# Sensor_Board_0x07_Heat_Flux_v2.net
KiCad netlist of a schematic drawn in EAGLE
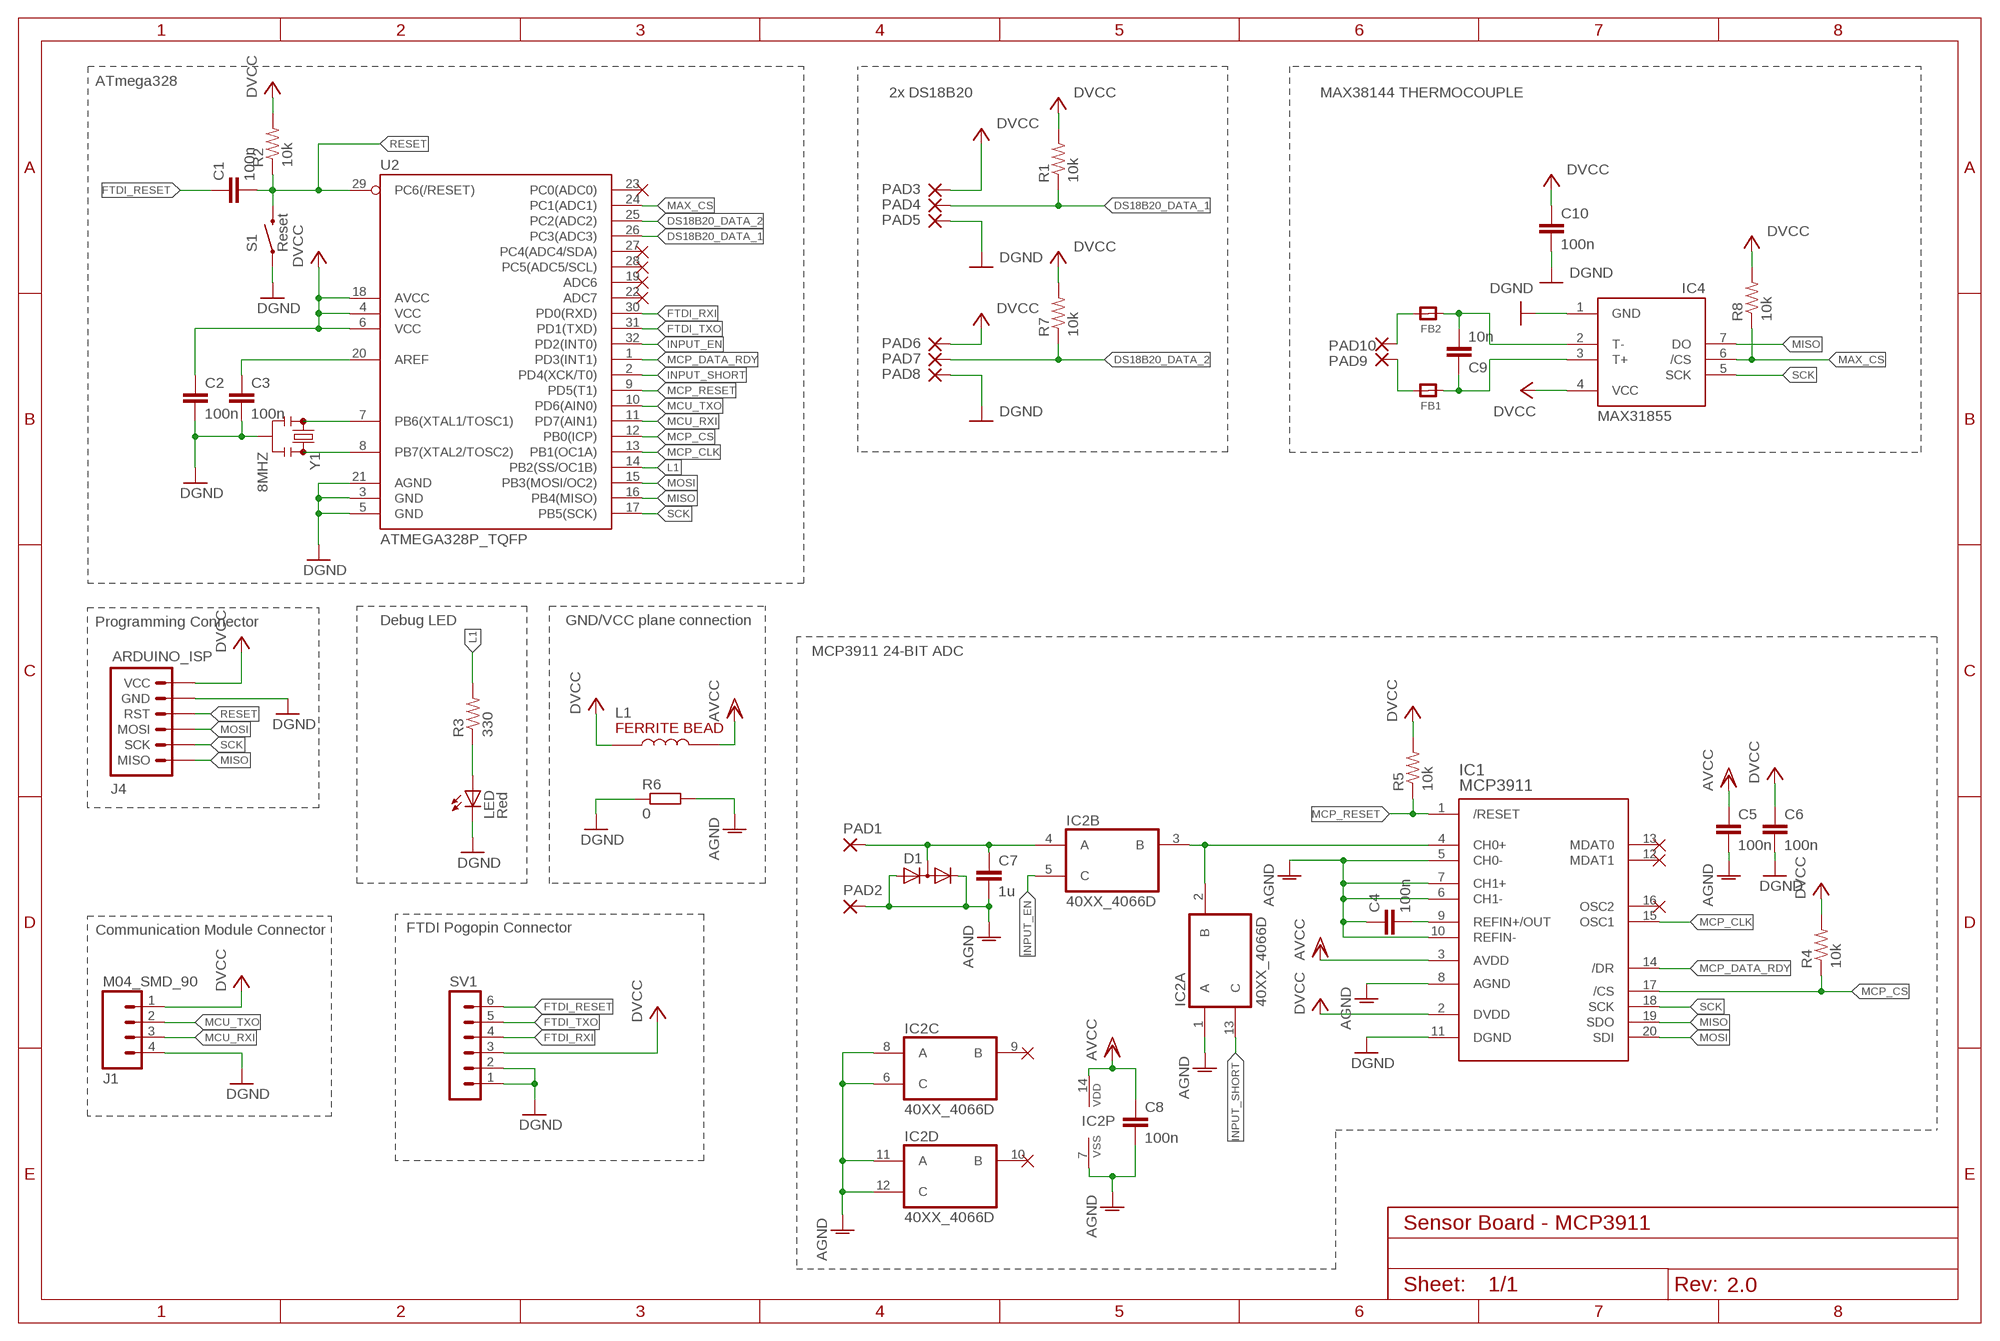
[diagram p0: schematic, sheet 1]

(export (version "E")
  (design (tool "Eeschema 10.0.6"))
  (components
    (comp (ref "C1")
      (value "100n")
      (footprint "eagle-import:C0805")
      (libsource (lib "eagle-import") (part "C"))
    )
    (comp (ref "C2")
      (value "100n")
      (footprint "eagle-import:C0805")
      (libsource (lib "eagle-import") (part "C"))
    )
    (comp (ref "C3")
      (value "100n")
      (footprint "eagle-import:C0805")
      (libsource (lib "eagle-import") (part "C"))
    )
    (comp (ref "C4")
      (value "100n")
      (footprint "eagle-import:C0805")
      (libsource (lib "eagle-import") (part "C"))
    )
    (comp (ref "C5")
      (value "100n")
      (footprint "eagle-import:C0805")
      (libsource (lib "eagle-import") (part "C"))
    )
    (comp (ref "C6")
      (value "100n")
      (footprint "eagle-import:C0805")
      (libsource (lib "eagle-import") (part "C"))
    )
    (comp (ref "C7")
      (value "1u")
      (footprint "eagle-import:C0805")
      (libsource (lib "eagle-import") (part "C"))
    )
    (comp (ref "C8")
      (value "100n")
      (footprint "eagle-import:C0805")
      (libsource (lib "eagle-import") (part "C"))
    )
    (comp (ref "C9")
      (value "10n")
      (footprint "eagle-import:C0805")
      (libsource (lib "eagle-import") (part "C"))
    )
    (comp (ref "C10")
      (value "100n")
      (footprint "eagle-import:C0805")
      (libsource (lib "eagle-import") (part "C"))
    )
    (comp (ref "D1")
      (value "LEDXLAMP_BAV99")
      (footprint "eagle-import:LEDXLAMP_SOT23")
      (libsource (lib "eagle-import") (part "LEDXLAMP_BAV99"))
    )
    (comp (ref "FB1")
      (value "MICROBUILDER_FERRITE_0805MP")
      (footprint "eagle-import:MICROBUILDER__0805MP")
      (libsource (lib "eagle-import") (part "MICROBUILDER_FERRITE_0805MP"))
    )
    (comp (ref "FB2")
      (value "MICROBUILDER_FERRITE_0805MP")
      (footprint "eagle-import:MICROBUILDER__0805MP")
      (libsource (lib "eagle-import") (part "MICROBUILDER_FERRITE_0805MP"))
    )
    (comp (ref "IC1")
      (value "MCP3911")
      (footprint "eagle-import:HEATFLOW_SSOP20")
      (libsource (lib "eagle-import") (part "HEATFLOW_MCP3911A0-E/SS"))
    )
    (comp (ref "IC2")
      (value "40XX_4066D")
      (footprint "eagle-import:40XX_SO14")
      (libsource (lib "eagle-import") (part "40XX_4066D"))
    )
    (comp (ref "IC4")
      (value "MAX31855")
      (footprint "eagle-import:ADAFRUIT_SO08")
      (libsource (lib "eagle-import") (part "ADAFRUIT_MAX31855"))
    )
    (comp (ref "J1")
      (value "M04_SMD_90")
      (footprint "eagle-import:M04_SMD_90")
      (libsource (lib "eagle-import") (part "M04_SMD_90"))
    )
    (comp (ref "J4")
      (value "ARDUINO_ISP")
      (footprint "eagle-import:M-2X3")
      (libsource (lib "eagle-import") (part "ARDUINO_ISP"))
    )
    (comp (ref "L1")
      (value "HEATFLOW2_74279220601")
      (footprint "eagle-import:HEATFLOW2_0805")
      (libsource (lib "eagle-import") (part "HEATFLOW2_74279220601"))
    )
    (comp (ref "LED")
      (value "Red")
      (footprint "eagle-import:SML0805")
      (libsource (lib "eagle-import") (part "LEDSML0805"))
    )
    (comp (ref "PAD1")
      (value "WIREPADSMD1,27-254")
      (footprint "eagle-import:SMD1,27-2,54")
      (libsource (lib "eagle-import") (part "WIREPADSMD1,27-254"))
    )
    (comp (ref "PAD2")
      (value "WIREPADSMD1,27-254")
      (footprint "eagle-import:SMD1,27-2,54")
      (libsource (lib "eagle-import") (part "WIREPADSMD1,27-254"))
    )
    (comp (ref "PAD3")
      (value "WIREPADSMD1,27-254")
      (footprint "eagle-import:SMD1,27-2,54")
      (libsource (lib "eagle-import") (part "WIREPADSMD1,27-254"))
    )
    (comp (ref "PAD4")
      (value "WIREPADSMD1,27-254")
      (footprint "eagle-import:SMD1,27-2,54")
      (libsource (lib "eagle-import") (part "WIREPADSMD1,27-254"))
    )
    (comp (ref "PAD5")
      (value "WIREPADSMD1,27-254")
      (footprint "eagle-import:SMD1,27-2,54")
      (libsource (lib "eagle-import") (part "WIREPADSMD1,27-254"))
    )
    (comp (ref "PAD6")
      (value "WIREPADSMD1,27-254")
      (footprint "eagle-import:SMD1,27-2,54")
      (libsource (lib "eagle-import") (part "WIREPADSMD1,27-254"))
    )
    (comp (ref "PAD7")
      (value "WIREPADSMD1,27-254")
      (footprint "eagle-import:SMD1,27-2,54")
      (libsource (lib "eagle-import") (part "WIREPADSMD1,27-254"))
    )
    (comp (ref "PAD8")
      (value "WIREPADSMD1,27-254")
      (footprint "eagle-import:SMD1,27-2,54")
      (libsource (lib "eagle-import") (part "WIREPADSMD1,27-254"))
    )
    (comp (ref "PAD9")
      (value "WIREPADSMD1,27-254")
      (footprint "eagle-import:SMD1,27-2,54")
      (libsource (lib "eagle-import") (part "WIREPADSMD1,27-254"))
    )
    (comp (ref "PAD10")
      (value "WIREPADSMD1,27-254")
      (footprint "eagle-import:SMD1,27-2,54")
      (libsource (lib "eagle-import") (part "WIREPADSMD1,27-254"))
    )
    (comp (ref "R1")
      (value "10k")
      (footprint "eagle-import:0805")
      (libsource (lib "eagle-import") (part "RESISTOR0805-RES"))
    )
    (comp (ref "R2")
      (value "10k")
      (footprint "eagle-import:0805")
      (libsource (lib "eagle-import") (part "RESISTOR0805-RES"))
    )
    (comp (ref "R3")
      (value "330")
      (footprint "eagle-import:0805")
      (libsource (lib "eagle-import") (part "RESISTOR0805-RES"))
    )
    (comp (ref "R4")
      (value "10k")
      (footprint "eagle-import:0805")
      (libsource (lib "eagle-import") (part "RESISTOR0805-RES"))
    )
    (comp (ref "R5")
      (value "10k")
      (footprint "eagle-import:0805")
      (libsource (lib "eagle-import") (part "RESISTOR0805-RES"))
    )
    (comp (ref "R6")
      (value "0")
      (footprint "eagle-import:RESISTOR_M0805")
      (libsource (lib "eagle-import") (part "RESISTOR_R-EU_M0805"))
    )
    (comp (ref "R7")
      (value "10k")
      (footprint "eagle-import:0805")
      (libsource (lib "eagle-import") (part "RESISTOR0805-RES"))
    )
    (comp (ref "R8")
      (value "10k")
      (footprint "eagle-import:0805")
      (libsource (lib "eagle-import") (part "RESISTOR0805-RES"))
    )
    (comp (ref "S1")
      (value "Reset")
      (footprint "eagle-import:M-PUSHBUTTON-SMD")
      (libsource (lib "eagle-import") (part "PUSHBUTTON"))
    )
    (comp (ref "SV1")
      (value "MA06-1")
      (footprint "eagle-import:MA06-1")
      (libsource (lib "eagle-import") (part "MA06-1"))
    )
    (comp (ref "U2")
      (value "ATMEGA328P_TQFP")
      (footprint "eagle-import:TQFP32-08")
      (libsource (lib "eagle-import") (part "ATMEGA328P_TQFP"))
    )
    (comp (ref "Y1")
      (value "8MHZ")
      (footprint "eagle-import:RESONATOR-SMD")
      (libsource (lib "eagle-import") (part "RESONATOR8MHZ"))
    )
  )
  (nets
    (net (code "1") (name "AGND") (class "Default")
      (node (ref "C4") (pin "1") (pinfunction "1_1") (pintype "passive"))
      (node (ref "C5") (pin "2") (pinfunction "2_2") (pintype "passive"))
      (node (ref "C7") (pin "2") (pinfunction "2_2") (pintype "passive"))
      (node (ref "C8") (pin "2") (pinfunction "2_2") (pintype "passive"))
      (node (ref "D1") (pin "1") (pinfunction "A_1") (pintype "passive"))
      (node (ref "D1") (pin "2") (pinfunction "C_2") (pintype "passive"))
      (node (ref "IC1") (pin "10") (pinfunction "REFIN-_10") (pintype "bidirectional"))
      (node (ref "IC1") (pin "5") (pinfunction "CH0-_5") (pintype "bidirectional"))
      (node (ref "IC1") (pin "6") (pinfunction "CH1-_6") (pintype "bidirectional"))
      (node (ref "IC1") (pin "7") (pinfunction "CH1+_7") (pintype "bidirectional"))
      (node (ref "IC1") (pin "8") (pinfunction "AGND_8") (pintype "bidirectional"))
      (node (ref "IC2") (pin "1") (pinfunction "A_1") (pintype "tri_state"))
      (node (ref "IC2") (pin "11") (pinfunction "A_11") (pintype "tri_state"))
      (node (ref "IC2") (pin "12") (pinfunction "C_12") (pintype "input"))
      (node (ref "IC2") (pin "6") (pinfunction "C_6") (pintype "input"))
      (node (ref "IC2") (pin "7") (pinfunction "VSS_7") (pintype "power_in"))
      (node (ref "IC2") (pin "8") (pinfunction "A_8") (pintype "tri_state"))
      (node (ref "PAD2") (pin "1") (pinfunction "P_1") (pintype "passive"))
      (node (ref "R6") (pin "2") (pinfunction "2_2") (pintype "passive"))
    )
    (net (code "2") (name "AVCC") (class "Default")
      (node (ref "C5") (pin "1") (pinfunction "1_1") (pintype "passive"))
      (node (ref "C8") (pin "1") (pinfunction "1_1") (pintype "passive"))
      (node (ref "IC1") (pin "3") (pinfunction "AVDD_3") (pintype "bidirectional"))
      (node (ref "IC2") (pin "14") (pinfunction "VDD_14") (pintype "power_in"))
      (node (ref "L1") (pin "2") (pinfunction "P$2_2") (pintype "bidirectional"))
    )
    (net (code "3") (name "DGND") (class "Default")
      (node (ref "C10") (pin "2") (pinfunction "2_2") (pintype "passive"))
      (node (ref "C2") (pin "2") (pinfunction "2_2") (pintype "passive"))
      (node (ref "C3") (pin "2") (pinfunction "2_2") (pintype "passive"))
      (node (ref "C6") (pin "2") (pinfunction "2_2") (pintype "passive"))
      (node (ref "IC1") (pin "11") (pinfunction "DGND_11") (pintype "bidirectional"))
      (node (ref "IC4") (pin "1") (pinfunction "GND_1") (pintype "power_in"))
      (node (ref "J1") (pin "4") (pinfunction "4_4") (pintype "passive"))
      (node (ref "J4") (pin "P$5") (pinfunction "GND_P$5") (pintype "passive"))
      (node (ref "LED") (pin "C") (pinfunction "C_C") (pintype "passive"))
      (node (ref "PAD5") (pin "1") (pinfunction "P_1") (pintype "passive"))
      (node (ref "PAD8") (pin "1") (pinfunction "P_1") (pintype "passive"))
      (node (ref "R6") (pin "1") (pinfunction "1_1") (pintype "passive"))
      (node (ref "S1") (pin "1") (pinfunction "LEFT_1") (pintype "passive"))
      (node (ref "S1") (pin "2") (pinfunction "LEFT_2") (pintype "passive"))
      (node (ref "SV1") (pin "1") (pinfunction "1_1") (pintype "passive"))
      (node (ref "SV1") (pin "2") (pinfunction "2_2") (pintype "passive"))
      (node (ref "U2") (pin "21") (pinfunction "AGND_21") (pintype "bidirectional"))
      (node (ref "U2") (pin "3") (pinfunction "GND_3") (pintype "bidirectional"))
      (node (ref "U2") (pin "5") (pinfunction "GND_5") (pintype "bidirectional"))
      (node (ref "Y1") (pin "2") (pinfunction "2_2") (pintype "passive"))
    )
    (net (code "4") (name "DS18B20_DATA_1") (class "Default")
      (node (ref "PAD4") (pin "1") (pinfunction "P_1") (pintype "passive"))
      (node (ref "R1") (pin "1") (pinfunction "1_1") (pintype "passive"))
      (node (ref "U2") (pin "26") (pinfunction "PC3(ADC3)_26") (pintype "bidirectional"))
    )
    (net (code "5") (name "DS18B20_DATA_2") (class "Default")
      (node (ref "PAD7") (pin "1") (pinfunction "P_1") (pintype "passive"))
      (node (ref "R7") (pin "1") (pinfunction "1_1") (pintype "passive"))
      (node (ref "U2") (pin "25") (pinfunction "PC2(ADC2)_25") (pintype "bidirectional"))
    )
    (net (code "6") (name "DVCC") (class "Default")
      (node (ref "C10") (pin "1") (pinfunction "1_1") (pintype "passive"))
      (node (ref "C2") (pin "1") (pinfunction "1_1") (pintype "passive"))
      (node (ref "C6") (pin "1") (pinfunction "1_1") (pintype "passive"))
      (node (ref "IC1") (pin "2") (pinfunction "DVDD_2") (pintype "bidirectional"))
      (node (ref "IC4") (pin "4") (pinfunction "VCC_4") (pintype "power_in"))
      (node (ref "J1") (pin "1") (pinfunction "1_1") (pintype "passive"))
      (node (ref "J4") (pin "P$6") (pinfunction "VCC_P$6") (pintype "passive"))
      (node (ref "L1") (pin "1") (pinfunction "P$1_1") (pintype "bidirectional"))
      (node (ref "PAD3") (pin "1") (pinfunction "P_1") (pintype "passive"))
      (node (ref "PAD6") (pin "1") (pinfunction "P_1") (pintype "passive"))
      (node (ref "R1") (pin "2") (pinfunction "2_2") (pintype "passive"))
      (node (ref "R2") (pin "2") (pinfunction "2_2") (pintype "passive"))
      (node (ref "R4") (pin "2") (pinfunction "2_2") (pintype "passive"))
      (node (ref "R5") (pin "2") (pinfunction "2_2") (pintype "passive"))
      (node (ref "R7") (pin "2") (pinfunction "2_2") (pintype "passive"))
      (node (ref "R8") (pin "2") (pinfunction "2_2") (pintype "passive"))
      (node (ref "SV1") (pin "3") (pinfunction "3_3") (pintype "passive"))
      (node (ref "U2") (pin "18") (pinfunction "AVCC_18") (pintype "bidirectional"))
      (node (ref "U2") (pin "4") (pinfunction "VCC_4") (pintype "bidirectional"))
      (node (ref "U2") (pin "6") (pinfunction "VCC_6") (pintype "bidirectional"))
    )
    (net (code "7") (name "FTDI_RESET") (class "Default")
      (node (ref "C1") (pin "1") (pinfunction "1_1") (pintype "passive"))
      (node (ref "SV1") (pin "6") (pinfunction "6_6") (pintype "passive"))
    )
    (net (code "8") (name "FTDI_RXI") (class "Default")
      (node (ref "SV1") (pin "4") (pinfunction "4_4") (pintype "passive"))
      (node (ref "U2") (pin "30") (pinfunction "PD0(RXD)_30") (pintype "bidirectional"))
    )
    (net (code "9") (name "FTDI_TXO") (class "Default")
      (node (ref "SV1") (pin "5") (pinfunction "5_5") (pintype "passive"))
      (node (ref "U2") (pin "31") (pinfunction "PD1(TXD)_31") (pintype "bidirectional"))
    )
    (net (code "10") (name "INPUT_EN") (class "Default")
      (node (ref "IC2") (pin "5") (pinfunction "C_5") (pintype "input"))
      (node (ref "U2") (pin "32") (pinfunction "PD2(INT0)_32") (pintype "bidirectional"))
    )
    (net (code "11") (name "INPUT_SHORT") (class "Default")
      (node (ref "IC2") (pin "13") (pinfunction "C_13") (pintype "input"))
      (node (ref "U2") (pin "2") (pinfunction "PD4(XCK/T0)_2") (pintype "bidirectional"))
    )
    (net (code "12") (name "L1") (class "Default")
      (node (ref "R3") (pin "2") (pinfunction "2_2") (pintype "passive"))
      (node (ref "U2") (pin "14") (pinfunction "PB2(SS/OC1B)_14") (pintype "bidirectional"))
    )
    (net (code "13") (name "MAX_CS") (class "Default")
      (node (ref "IC4") (pin "6") (pinfunction "/CS_6") (pintype "input"))
      (node (ref "R8") (pin "1") (pinfunction "1_1") (pintype "passive"))
      (node (ref "U2") (pin "24") (pinfunction "PC1(ADC1)_24") (pintype "bidirectional"))
    )
    (net (code "14") (name "MCP_CLK") (class "Default")
      (node (ref "IC1") (pin "15") (pinfunction "OSC1_15") (pintype "bidirectional"))
      (node (ref "U2") (pin "13") (pinfunction "PB1(OC1A)_13") (pintype "bidirectional"))
    )
    (net (code "15") (name "MCP_CS") (class "Default")
      (node (ref "IC1") (pin "17") (pinfunction "/CS_17") (pintype "bidirectional"))
      (node (ref "R4") (pin "1") (pinfunction "1_1") (pintype "passive"))
      (node (ref "U2") (pin "12") (pinfunction "PB0(ICP)_12") (pintype "bidirectional"))
    )
    (net (code "16") (name "MCP_DATA_RDY") (class "Default")
      (node (ref "IC1") (pin "14") (pinfunction "/DR_14") (pintype "bidirectional"))
      (node (ref "U2") (pin "1") (pinfunction "PD3(INT1)_1") (pintype "bidirectional"))
    )
    (net (code "17") (name "MCP_RESET") (class "Default")
      (node (ref "IC1") (pin "1") (pinfunction "/RESET_1") (pintype "bidirectional"))
      (node (ref "R5") (pin "1") (pinfunction "1_1") (pintype "passive"))
      (node (ref "U2") (pin "9") (pinfunction "PD5(T1)_9") (pintype "bidirectional"))
    )
    (net (code "18") (name "MCU_RXI") (class "Default")
      (node (ref "J1") (pin "3") (pinfunction "3_3") (pintype "passive"))
      (node (ref "U2") (pin "11") (pinfunction "PD7(AIN1)_11") (pintype "bidirectional"))
    )
    (net (code "19") (name "MCU_TXO") (class "Default")
      (node (ref "J1") (pin "2") (pinfunction "2_2") (pintype "passive"))
      (node (ref "U2") (pin "10") (pinfunction "PD6(AIN0)_10") (pintype "bidirectional"))
    )
    (net (code "20") (name "MISO") (class "Default")
      (node (ref "IC1") (pin "19") (pinfunction "SDO_19") (pintype "bidirectional"))
      (node (ref "IC4") (pin "7") (pinfunction "DO_7") (pintype "output"))
      (node (ref "J4") (pin "P$1") (pinfunction "MISO_P$1") (pintype "passive"))
      (node (ref "U2") (pin "16") (pinfunction "PB4(MISO)_16") (pintype "bidirectional"))
    )
    (net (code "21") (name "MOSI") (class "Default")
      (node (ref "IC1") (pin "20") (pinfunction "SDI_20") (pintype "bidirectional"))
      (node (ref "J4") (pin "P$3") (pinfunction "MOSI_P$3") (pintype "passive"))
      (node (ref "U2") (pin "15") (pinfunction "PB3(MOSI/OC2)_15") (pintype "bidirectional"))
    )
    (net (code "22") (name "Net-(D1-AC)") (class "Default")
      (node (ref "C7") (pin "1") (pinfunction "1_1") (pintype "passive"))
      (node (ref "D1") (pin "3") (pinfunction "AC_3") (pintype "passive"))
      (node (ref "IC2") (pin "4") (pinfunction "A_4") (pintype "tri_state"))
      (node (ref "PAD1") (pin "1") (pinfunction "P_1") (pintype "passive"))
    )
    (net (code "23") (name "Net-(FB1-P$1)") (class "Default")
      (node (ref "FB1") (pin "1") (pinfunction "P$1_1") (pintype "passive"))
      (node (ref "PAD9") (pin "1") (pinfunction "P_1") (pintype "passive"))
    )
    (net (code "24") (name "Net-(FB1-P$2)") (class "Default")
      (node (ref "C9") (pin "1") (pinfunction "1_1") (pintype "passive"))
      (node (ref "FB1") (pin "2") (pinfunction "P$2_2") (pintype "passive"))
      (node (ref "IC4") (pin "3") (pinfunction "T+_3") (pintype "input"))
    )
    (net (code "25") (name "Net-(FB2-P$1)") (class "Default")
      (node (ref "FB2") (pin "1") (pinfunction "P$1_1") (pintype "passive"))
      (node (ref "PAD10") (pin "1") (pinfunction "P_1") (pintype "passive"))
    )
    (net (code "26") (name "Net-(FB2-P$2)") (class "Default")
      (node (ref "C9") (pin "2") (pinfunction "2_2") (pintype "passive"))
      (node (ref "FB2") (pin "2") (pinfunction "P$2_2") (pintype "passive"))
      (node (ref "IC4") (pin "2") (pinfunction "T-_2") (pintype "input"))
    )
    (net (code "27") (name "Net-(IC1-CH0+)") (class "Default")
      (node (ref "IC1") (pin "4") (pinfunction "CH0+_4") (pintype "bidirectional"))
      (node (ref "IC2") (pin "2") (pinfunction "B_2") (pintype "tri_state"))
      (node (ref "IC2") (pin "3") (pinfunction "B_3") (pintype "tri_state"))
    )
    (net (code "28") (name "Net-(IC1-REFIN+{slash}OUT)") (class "Default")
      (node (ref "C4") (pin "2") (pinfunction "2_2") (pintype "passive"))
      (node (ref "IC1") (pin "9") (pinfunction "REFIN+/OUT_9") (pintype "bidirectional"))
    )
    (net (code "29") (name "Net-(LED-PadA)") (class "Default")
      (node (ref "LED") (pin "A") (pinfunction "A_A") (pintype "passive"))
      (node (ref "R3") (pin "1") (pinfunction "1_1") (pintype "passive"))
    )
    (net (code "30") (name "Net-(U2-AREF)") (class "Default")
      (node (ref "C3") (pin "1") (pinfunction "1_1") (pintype "passive"))
      (node (ref "U2") (pin "20") (pinfunction "AREF_20") (pintype "bidirectional"))
    )
    (net (code "31") (name "Net-(U2-PB6(XTAL1{slash}TOSC1))") (class "Default")
      (node (ref "U2") (pin "7") (pinfunction "PB6(XTAL1/TOSC1)_7") (pintype "bidirectional"))
      (node (ref "Y1") (pin "1") (pinfunction "1_1") (pintype "passive"))
    )
    (net (code "32") (name "Net-(U2-PB7(XTAL2{slash}TOSC2))") (class "Default")
      (node (ref "U2") (pin "8") (pinfunction "PB7(XTAL2/TOSC2)_8") (pintype "bidirectional"))
      (node (ref "Y1") (pin "3") (pinfunction "3_3") (pintype "passive"))
    )
    (net (code "33") (name "RESET") (class "Default")
      (node (ref "C1") (pin "2") (pinfunction "2_2") (pintype "passive"))
      (node (ref "J4") (pin "P$4") (pinfunction "RST_P$4") (pintype "passive"))
      (node (ref "R2") (pin "1") (pinfunction "1_1") (pintype "passive"))
      (node (ref "S1") (pin "3") (pinfunction "RIGHT_3") (pintype "passive"))
      (node (ref "S1") (pin "4") (pinfunction "RIGHT_4") (pintype "passive"))
      (node (ref "U2") (pin "29") (pinfunction "PC6(/RESET)_29") (pintype "bidirectional"))
    )
    (net (code "34") (name "SCK") (class "Default")
      (node (ref "IC1") (pin "18") (pinfunction "SCK_18") (pintype "bidirectional"))
      (node (ref "IC4") (pin "5") (pinfunction "SCK_5") (pintype "input"))
      (node (ref "J4") (pin "P$2") (pinfunction "SCK_P$2") (pintype "passive"))
      (node (ref "U2") (pin "17") (pinfunction "PB5(SCK)_17") (pintype "bidirectional"))
    )
    (net (code "35") (name "unconnected-(IC1-MDAT0-Pad13)") (class "Default")
      (node (ref "IC1") (pin "13") (pinfunction "MDAT0_13") (pintype "bidirectional"))
    )
    (net (code "36") (name "unconnected-(IC1-MDAT1-Pad12)") (class "Default")
      (node (ref "IC1") (pin "12") (pinfunction "MDAT1_12") (pintype "bidirectional"))
    )
    (net (code "37") (name "unconnected-(IC1-OSC2-Pad16)") (class "Default")
      (node (ref "IC1") (pin "16") (pinfunction "OSC2_16") (pintype "bidirectional"))
    )
    (net (code "38") (name "unconnected-(IC2C-B-Pad9)") (class "Default")
      (node (ref "IC2") (pin "9") (pinfunction "B_9") (pintype "tri_state"))
    )
    (net (code "39") (name "unconnected-(IC2D-B-Pad10)") (class "Default")
      (node (ref "IC2") (pin "10") (pinfunction "B_10") (pintype "tri_state"))
    )
    (net (code "40") (name "unconnected-(U2-ADC6-Pad19)") (class "Default")
      (node (ref "U2") (pin "19") (pinfunction "ADC6_19") (pintype "bidirectional"))
    )
    (net (code "41") (name "unconnected-(U2-ADC7-Pad22)") (class "Default")
      (node (ref "U2") (pin "22") (pinfunction "ADC7_22") (pintype "bidirectional"))
    )
    (net (code "42") (name "unconnected-(U2-PC0(ADC0)-Pad23)") (class "Default")
      (node (ref "U2") (pin "23") (pinfunction "PC0(ADC0)_23") (pintype "bidirectional"))
    )
    (net (code "43") (name "unconnected-(U2-PC4(ADC4{slash}SDA)-Pad27)") (class "Default")
      (node (ref "U2") (pin "27") (pinfunction "PC4(ADC4/SDA)_27") (pintype "bidirectional"))
    )
    (net (code "44") (name "unconnected-(U2-PC5(ADC5{slash}SCL)-Pad28)") (class "Default")
      (node (ref "U2") (pin "28") (pinfunction "PC5(ADC5/SCL)_28") (pintype "bidirectional"))
    )
  )
)
